# ecu2_telemetria.net
KiCad netlist of a schematic drawn in EAGLE
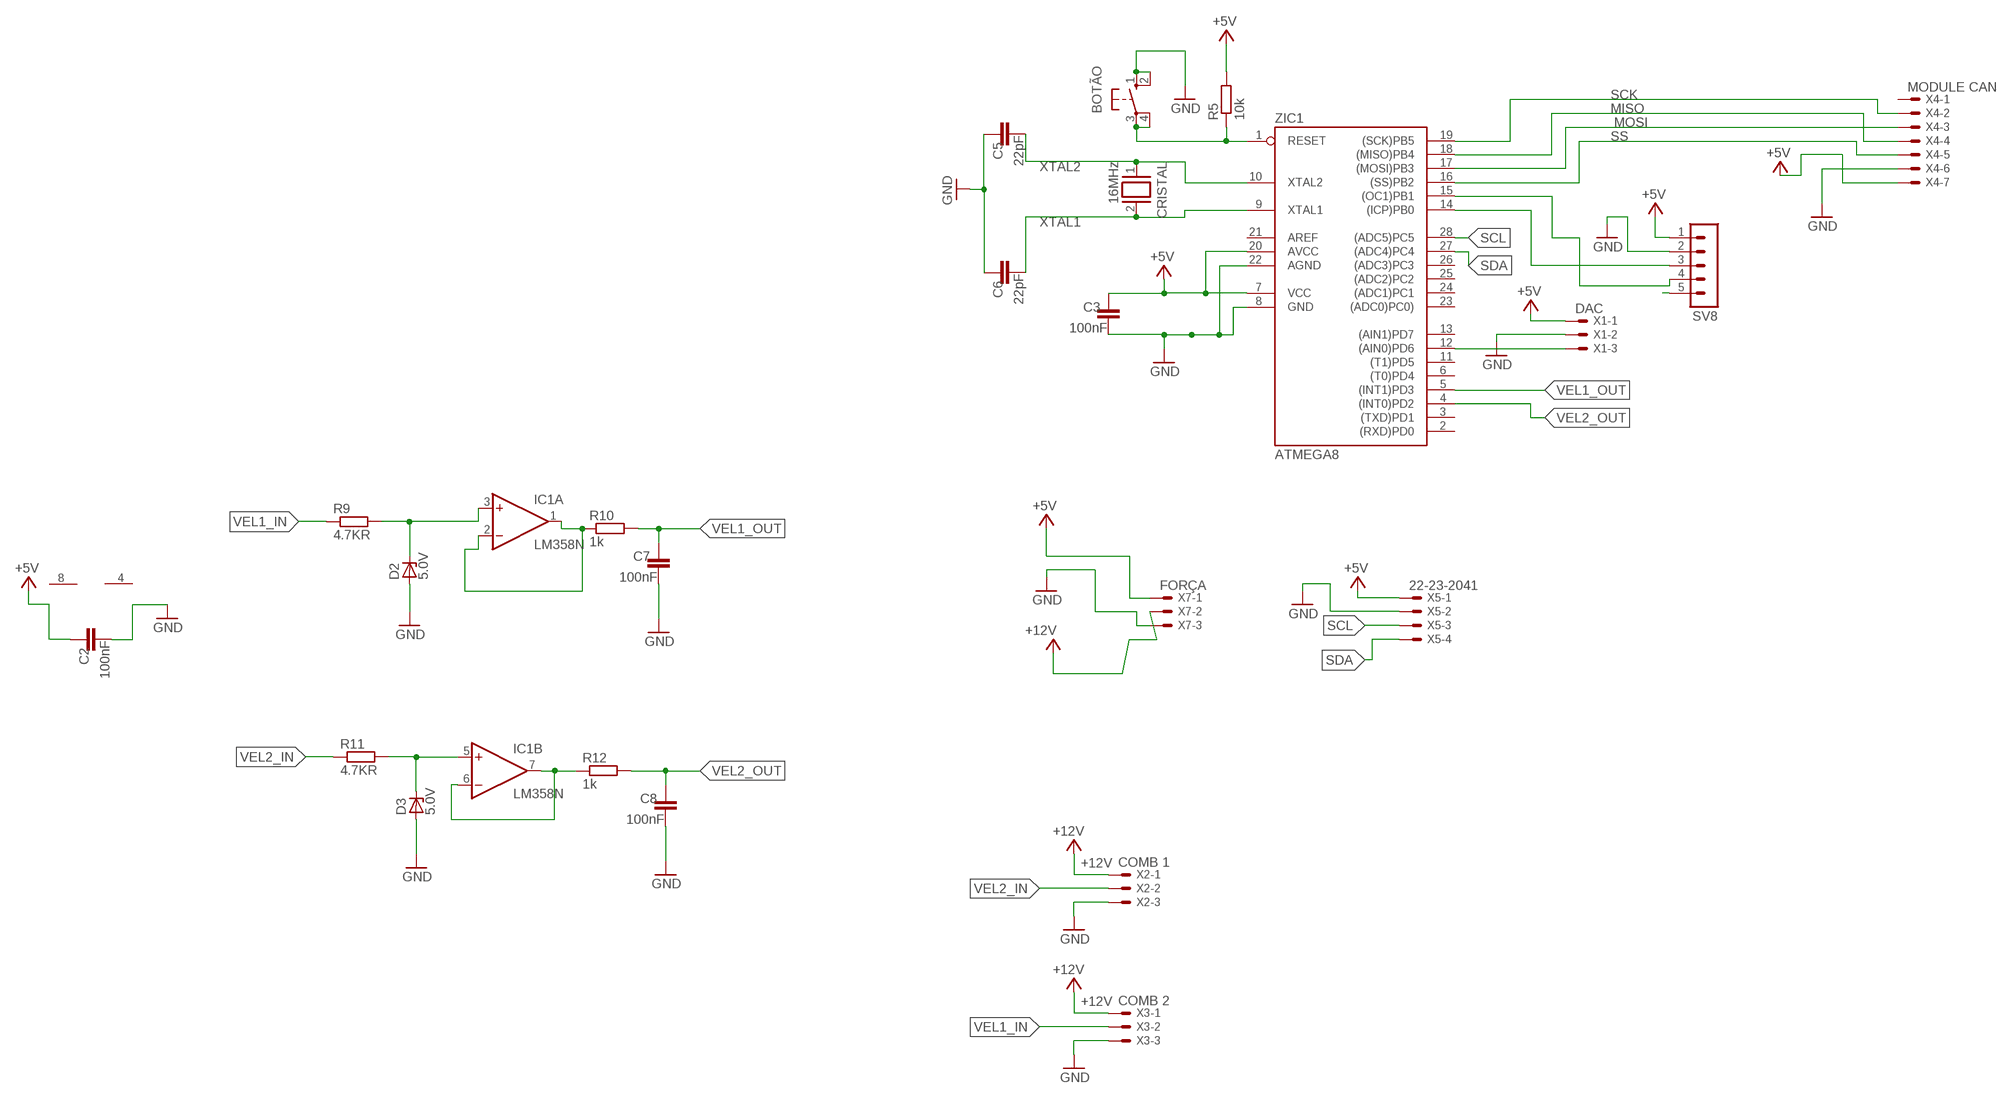
[diagram p0: schematic, sheet 1]

(export (version "E")
  (design (tool "Eeschema 10.0.6"))
  (components
    (comp (ref "BOTÃO")
      (value "10-XX")
      (footprint "eagle-import:B3F-10XX")
      (fields (field (name "MPN") "B3F-1000"))
      (libsource (lib "eagle-import") (part "10-XX"))
    )
    (comp (ref "C2")
      (value "100nF")
      (footprint "eagle-import:C5B2.5")
      (libsource (lib "eagle-import") (part "C5/2.5"))
    )
    (comp (ref "C3")
      (value "100nF")
      (footprint "eagle-import:C5B2.5")
      (libsource (lib "eagle-import") (part "C5/2.5"))
    )
    (comp (ref "C5")
      (value "22pF")
      (footprint "eagle-import:C5B2.5")
      (libsource (lib "eagle-import") (part "C5/2.5"))
    )
    (comp (ref "C6")
      (value "22pF")
      (footprint "eagle-import:C5B2.5")
      (libsource (lib "eagle-import") (part "C5/2.5"))
    )
    (comp (ref "C7")
      (value "100nF")
      (footprint "eagle-import:C5B2.5")
      (libsource (lib "eagle-import") (part "C5/2.5"))
    )
    (comp (ref "C8")
      (value "100nF")
      (footprint "eagle-import:C5B2.5")
      (libsource (lib "eagle-import") (part "C5/2.5"))
    )
    (comp (ref "CRISTAL")
      (value "16MHz")
      (footprint "eagle-import:QS")
      (libsource (lib "eagle-import") (part "XTAL/S"))
    )
    (comp (ref "D2")
      (value "5.0V")
      (footprint "eagle-import:DO34Z7")
      (libsource (lib "eagle-import") (part "ZENER-DIODEDO34-7"))
    )
    (comp (ref "D3")
      (value "5.0V")
      (footprint "eagle-import:DO34Z7")
      (libsource (lib "eagle-import") (part "ZENER-DIODEDO34-7"))
    )
    (comp (ref "IC1")
      (value "LM358N")
      (footprint "eagle-import:DIL08")
      (libsource (lib "eagle-import") (part "LM358N"))
    )
    (comp (ref "R5")
      (value "10k")
      (footprint "eagle-import:0207_7")
      (libsource (lib "eagle-import") (part "R-EU_0207/7"))
    )
    (comp (ref "R9")
      (value "4.7KR")
      (footprint "eagle-import:0207_7")
      (libsource (lib "eagle-import") (part "R-EU_0207/7"))
    )
    (comp (ref "R10")
      (value "1k")
      (footprint "eagle-import:0207_7")
      (libsource (lib "eagle-import") (part "R-EU_0207/7"))
    )
    (comp (ref "R11")
      (value "4.7KR")
      (footprint "eagle-import:0207_7")
      (libsource (lib "eagle-import") (part "R-EU_0207/7"))
    )
    (comp (ref "R12")
      (value "1k")
      (footprint "eagle-import:0207_7")
      (libsource (lib "eagle-import") (part "R-EU_0207/7"))
    )
    (comp (ref "SV8")
      (value "MA05-1")
      (footprint "eagle-import:MA05-1")
      (libsource (lib "eagle-import") (part "MA05-1"))
    )
    (comp (ref "X1")
      (value "DAC")
      (footprint "eagle-import:22-23-2031")
      (fields (field (name "MF") "MOLEX") (field (name "MPN") "22-23-2031"))
      (libsource (lib "eagle-import") (part "22-23-2031"))
    )
    (comp (ref "X2")
      (value "COMB 1")
      (footprint "eagle-import:22-23-2031")
      (fields (field (name "MF") "MOLEX") (field (name "MPN") "22-23-2031"))
      (libsource (lib "eagle-import") (part "22-23-2031"))
    )
    (comp (ref "X3")
      (value "COMB 2")
      (footprint "eagle-import:22-23-2031")
      (fields (field (name "MF") "MOLEX") (field (name "MPN") "22-23-2031"))
      (libsource (lib "eagle-import") (part "22-23-2031"))
    )
    (comp (ref "X4")
      (value "MODULE CAN")
      (footprint "eagle-import:22-23-2071")
      (fields (field (name "MF") "MOLEX") (field (name "MPN") "22-23-2071"))
      (libsource (lib "eagle-import") (part "22-23-2071"))
    )
    (comp (ref "X5")
      (value "22-23-2041")
      (footprint "eagle-import:22-23-2041")
      (fields (field (name "MF") "MOLEX"))
      (libsource (lib "eagle-import") (part "22-23-2041"))
    )
    (comp (ref "X7")
      (value "FORÇA")
      (footprint "eagle-import:22-23-2031")
      (fields (field (name "MF") "MOLEX") (field (name "MPN") "22-23-2031"))
      (libsource (lib "eagle-import") (part "22-23-2031"))
    )
    (comp (ref "ZIC1")
      (value "ATMEGA8")
      (footprint "eagle-import:DIL28-3")
      (libsource (lib "eagle-import") (part "AT90S4433P"))
    )
  )
  (nets
    (net (code "1") (name "+5V") (class "Default")
      (node (ref "C2") (pin "2") (pinfunction "2_2") (pintype "passive"))
      (node (ref "C3") (pin "2") (pinfunction "2_2") (pintype "passive"))
      (node (ref "R5") (pin "2") (pinfunction "2_2") (pintype "passive"))
      (node (ref "SV8") (pin "1") (pinfunction "1_1") (pintype "passive"))
      (node (ref "X1") (pin "1") (pinfunction "S_1") (pintype "passive"))
      (node (ref "X4") (pin "7") (pinfunction "S_7") (pintype "passive"))
      (node (ref "X5") (pin "1") (pinfunction "S_1") (pintype "passive"))
      (node (ref "X7") (pin "1") (pinfunction "S_1") (pintype "passive"))
      (node (ref "ZIC1") (pin "20") (pinfunction "AVCC_20") (pintype "power_in"))
      (node (ref "ZIC1") (pin "7") (pinfunction "VCC_7") (pintype "power_in"))
    )
    (net (code "2") (name "+12V") (class "Default")
      (node (ref "X2") (pin "1") (pinfunction "S_1") (pintype "passive"))
      (node (ref "X3") (pin "1") (pinfunction "S_1") (pintype "passive"))
      (node (ref "X7") (pin "2") (pinfunction "S_2") (pintype "passive"))
    )
    (net (code "3") (name "/MISO") (class "Default")
      (node (ref "X4") (pin "4") (pinfunction "S_4") (pintype "passive"))
      (node (ref "ZIC1") (pin "18") (pinfunction "(MISO)PB4_18") (pintype "bidirectional"))
    )
    (net (code "4") (name "/MOSI") (class "Default")
      (node (ref "X4") (pin "3") (pinfunction "S_3") (pintype "passive"))
      (node (ref "ZIC1") (pin "17") (pinfunction "(MOSI)PB3_17") (pintype "bidirectional"))
    )
    (net (code "5") (name "/SCK") (class "Default")
      (node (ref "X4") (pin "2") (pinfunction "S_2") (pintype "passive"))
      (node (ref "ZIC1") (pin "19") (pinfunction "(SCK)PB5_19") (pintype "bidirectional"))
    )
    (net (code "6") (name "/SS") (class "Default")
      (node (ref "X4") (pin "5") (pinfunction "S_5") (pintype "passive"))
      (node (ref "ZIC1") (pin "16") (pinfunction "(SS)PB2_16") (pintype "bidirectional"))
    )
    (net (code "7") (name "/V+") (class "Default")
      (node (ref "IC1") (pin "8") (pinfunction "V+_8") (pintype "power_in"))
    )
    (net (code "8") (name "/V-") (class "Default")
      (node (ref "IC1") (pin "4") (pinfunction "V-_4") (pintype "power_in"))
    )
    (net (code "9") (name "/XTAL1") (class "Default")
      (node (ref "C6") (pin "1") (pinfunction "1_1") (pintype "passive"))
      (node (ref "CRISTAL") (pin "2") (pinfunction "2_2") (pintype "passive"))
      (node (ref "ZIC1") (pin "9") (pinfunction "XTAL1_9") (pintype "bidirectional"))
    )
    (net (code "10") (name "/XTAL2") (class "Default")
      (node (ref "C5") (pin "1") (pinfunction "1_1") (pintype "passive"))
      (node (ref "CRISTAL") (pin "1") (pinfunction "1_1") (pintype "passive"))
      (node (ref "ZIC1") (pin "10") (pinfunction "XTAL2_10") (pintype "bidirectional"))
    )
    (net (code "11") (name "GND") (class "Default")
      (node (ref "BOTÃO") (pin "1") (pinfunction "S_1") (pintype "passive"))
      (node (ref "BOTÃO") (pin "2") (pinfunction "S1_2") (pintype "passive"))
      (node (ref "C2") (pin "1") (pinfunction "1_1") (pintype "passive"))
      (node (ref "C3") (pin "1") (pinfunction "1_1") (pintype "passive"))
      (node (ref "C5") (pin "2") (pinfunction "2_2") (pintype "passive"))
      (node (ref "C6") (pin "2") (pinfunction "2_2") (pintype "passive"))
      (node (ref "C7") (pin "1") (pinfunction "1_1") (pintype "passive"))
      (node (ref "C8") (pin "1") (pinfunction "1_1") (pintype "passive"))
      (node (ref "D2") (pin "A") (pinfunction "A_A") (pintype "passive"))
      (node (ref "D3") (pin "A") (pinfunction "A_A") (pintype "passive"))
      (node (ref "SV8") (pin "2") (pinfunction "2_2") (pintype "passive"))
      (node (ref "X1") (pin "2") (pinfunction "S_2") (pintype "passive"))
      (node (ref "X2") (pin "3") (pinfunction "S_3") (pintype "passive"))
      (node (ref "X3") (pin "3") (pinfunction "S_3") (pintype "passive"))
      (node (ref "X4") (pin "6") (pinfunction "S_6") (pintype "passive"))
      (node (ref "X5") (pin "2") (pinfunction "S_2") (pintype "passive"))
      (node (ref "X7") (pin "3") (pinfunction "S_3") (pintype "passive"))
      (node (ref "ZIC1") (pin "22") (pinfunction "AGND_22") (pintype "power_in"))
      (node (ref "ZIC1") (pin "8") (pinfunction "GND_8") (pintype "power_in"))
    )
    (net (code "12") (name "Net-(BOTÃO-P)") (class "Default")
      (node (ref "BOTÃO") (pin "3") (pinfunction "P_3") (pintype "passive"))
      (node (ref "BOTÃO") (pin "4") (pinfunction "P1_4") (pintype "passive"))
      (node (ref "R5") (pin "1") (pinfunction "1_1") (pintype "passive"))
      (node (ref "ZIC1") (pin "1") (pinfunction "RESET_1") (pintype "input"))
    )
    (net (code "13") (name "Net-(IC1A-+IN)") (class "Default")
      (node (ref "D2") (pin "C") (pinfunction "C_C") (pintype "passive"))
      (node (ref "IC1") (pin "3") (pinfunction "+IN_3") (pintype "input"))
      (node (ref "R9") (pin "2") (pinfunction "2_2") (pintype "passive"))
    )
    (net (code "14") (name "Net-(IC1A--IN)") (class "Default")
      (node (ref "IC1") (pin "1") (pinfunction "OUT_1") (pintype "output"))
      (node (ref "IC1") (pin "2") (pinfunction "-IN_2") (pintype "input"))
      (node (ref "R10") (pin "1") (pinfunction "1_1") (pintype "passive"))
    )
    (net (code "15") (name "Net-(IC1B-+IN)") (class "Default")
      (node (ref "D3") (pin "C") (pinfunction "C_C") (pintype "passive"))
      (node (ref "IC1") (pin "5") (pinfunction "+IN_5") (pintype "input"))
      (node (ref "R11") (pin "2") (pinfunction "2_2") (pintype "passive"))
    )
    (net (code "16") (name "Net-(IC1B--IN)") (class "Default")
      (node (ref "IC1") (pin "6") (pinfunction "-IN_6") (pintype "input"))
      (node (ref "IC1") (pin "7") (pinfunction "OUT_7") (pintype "output"))
      (node (ref "R12") (pin "1") (pinfunction "1_1") (pintype "passive"))
    )
    (net (code "17") (name "Net-(X1C-S)") (class "Default")
      (node (ref "X1") (pin "3") (pinfunction "S_3") (pintype "passive"))
      (node (ref "ZIC1") (pin "12") (pinfunction "(AIN0)PD6_12") (pintype "bidirectional"))
    )
    (net (code "18") (name "Net-(ZIC1-(ICP)PB0)") (class "Default")
      (node (ref "SV8") (pin "3") (pinfunction "3_3") (pintype "passive"))
      (node (ref "ZIC1") (pin "14") (pinfunction "(ICP)PB0_14") (pintype "bidirectional"))
    )
    (net (code "19") (name "Net-(ZIC1-(OC1)PB1)") (class "Default")
      (node (ref "SV8") (pin "4") (pinfunction "4_4") (pintype "passive"))
      (node (ref "ZIC1") (pin "15") (pinfunction "(OC1)PB1_15") (pintype "bidirectional"))
    )
    (net (code "20") (name "SCL") (class "Default")
      (node (ref "X5") (pin "3") (pinfunction "S_3") (pintype "passive"))
      (node (ref "ZIC1") (pin "28") (pinfunction "(ADC5)PC5_28") (pintype "bidirectional"))
    )
    (net (code "21") (name "SDA") (class "Default")
      (node (ref "X5") (pin "4") (pinfunction "S_4") (pintype "passive"))
      (node (ref "ZIC1") (pin "27") (pinfunction "(ADC4)PC4_27") (pintype "bidirectional"))
    )
    (net (code "22") (name "VEL1_IN") (class "Default")
      (node (ref "R9") (pin "1") (pinfunction "1_1") (pintype "passive"))
      (node (ref "X3") (pin "2") (pinfunction "S_2") (pintype "passive"))
    )
    (net (code "23") (name "VEL1_OUT") (class "Default")
      (node (ref "C7") (pin "2") (pinfunction "2_2") (pintype "passive"))
      (node (ref "R10") (pin "2") (pinfunction "2_2") (pintype "passive"))
      (node (ref "ZIC1") (pin "5") (pinfunction "(INT1)PD3_5") (pintype "bidirectional"))
    )
    (net (code "24") (name "VEL2_IN") (class "Default")
      (node (ref "R11") (pin "1") (pinfunction "1_1") (pintype "passive"))
      (node (ref "X2") (pin "2") (pinfunction "S_2") (pintype "passive"))
    )
    (net (code "25") (name "VEL2_OUT") (class "Default")
      (node (ref "C8") (pin "2") (pinfunction "2_2") (pintype "passive"))
      (node (ref "R12") (pin "2") (pinfunction "2_2") (pintype "passive"))
      (node (ref "ZIC1") (pin "4") (pinfunction "(INT0)PD2_4") (pintype "bidirectional"))
    )
    (net (code "26") (name "unconnected-(SV8-Pad5)") (class "Default")
      (node (ref "SV8") (pin "5") (pinfunction "5_5") (pintype "passive"))
    )
    (net (code "27") (name "unconnected-(X4A-S-Pad1)") (class "Default")
      (node (ref "X4") (pin "1") (pinfunction "S_1") (pintype "passive"))
    )
    (net (code "28") (name "unconnected-(ZIC1-(ADC0)PC0)-Pad23)") (class "Default")
      (node (ref "ZIC1") (pin "23") (pinfunction "(ADC0)PC0)_23") (pintype "bidirectional"))
    )
    (net (code "29") (name "unconnected-(ZIC1-(ADC1)PC1-Pad24)") (class "Default")
      (node (ref "ZIC1") (pin "24") (pinfunction "(ADC1)PC1_24") (pintype "bidirectional"))
    )
    (net (code "30") (name "unconnected-(ZIC1-(ADC2)PC2-Pad25)") (class "Default")
      (node (ref "ZIC1") (pin "25") (pinfunction "(ADC2)PC2_25") (pintype "bidirectional"))
    )
    (net (code "31") (name "unconnected-(ZIC1-(ADC3)PC3-Pad26)") (class "Default")
      (node (ref "ZIC1") (pin "26") (pinfunction "(ADC3)PC3_26") (pintype "bidirectional"))
    )
    (net (code "32") (name "unconnected-(ZIC1-(AIN1)PD7-Pad13)") (class "Default")
      (node (ref "ZIC1") (pin "13") (pinfunction "(AIN1)PD7_13") (pintype "bidirectional"))
    )
    (net (code "33") (name "unconnected-(ZIC1-(RXD)PD0-Pad2)") (class "Default")
      (node (ref "ZIC1") (pin "2") (pinfunction "(RXD)PD0_2") (pintype "bidirectional"))
    )
    (net (code "34") (name "unconnected-(ZIC1-(T0)PD4-Pad6)") (class "Default")
      (node (ref "ZIC1") (pin "6") (pinfunction "(T0)PD4_6") (pintype "bidirectional"))
    )
    (net (code "35") (name "unconnected-(ZIC1-(T1)PD5-Pad11)") (class "Default")
      (node (ref "ZIC1") (pin "11") (pinfunction "(T1)PD5_11") (pintype "bidirectional"))
    )
    (net (code "36") (name "unconnected-(ZIC1-(TXD)PD1-Pad3)") (class "Default")
      (node (ref "ZIC1") (pin "3") (pinfunction "(TXD)PD1_3") (pintype "bidirectional"))
    )
    (net (code "37") (name "unconnected-(ZIC1-AREF-Pad21)") (class "Default")
      (node (ref "ZIC1") (pin "21") (pinfunction "AREF_21") (pintype "passive"))
    )
  )
)
